# Panelizado_frentes.net
KiCad netlist of a schematic drawn in EAGLE
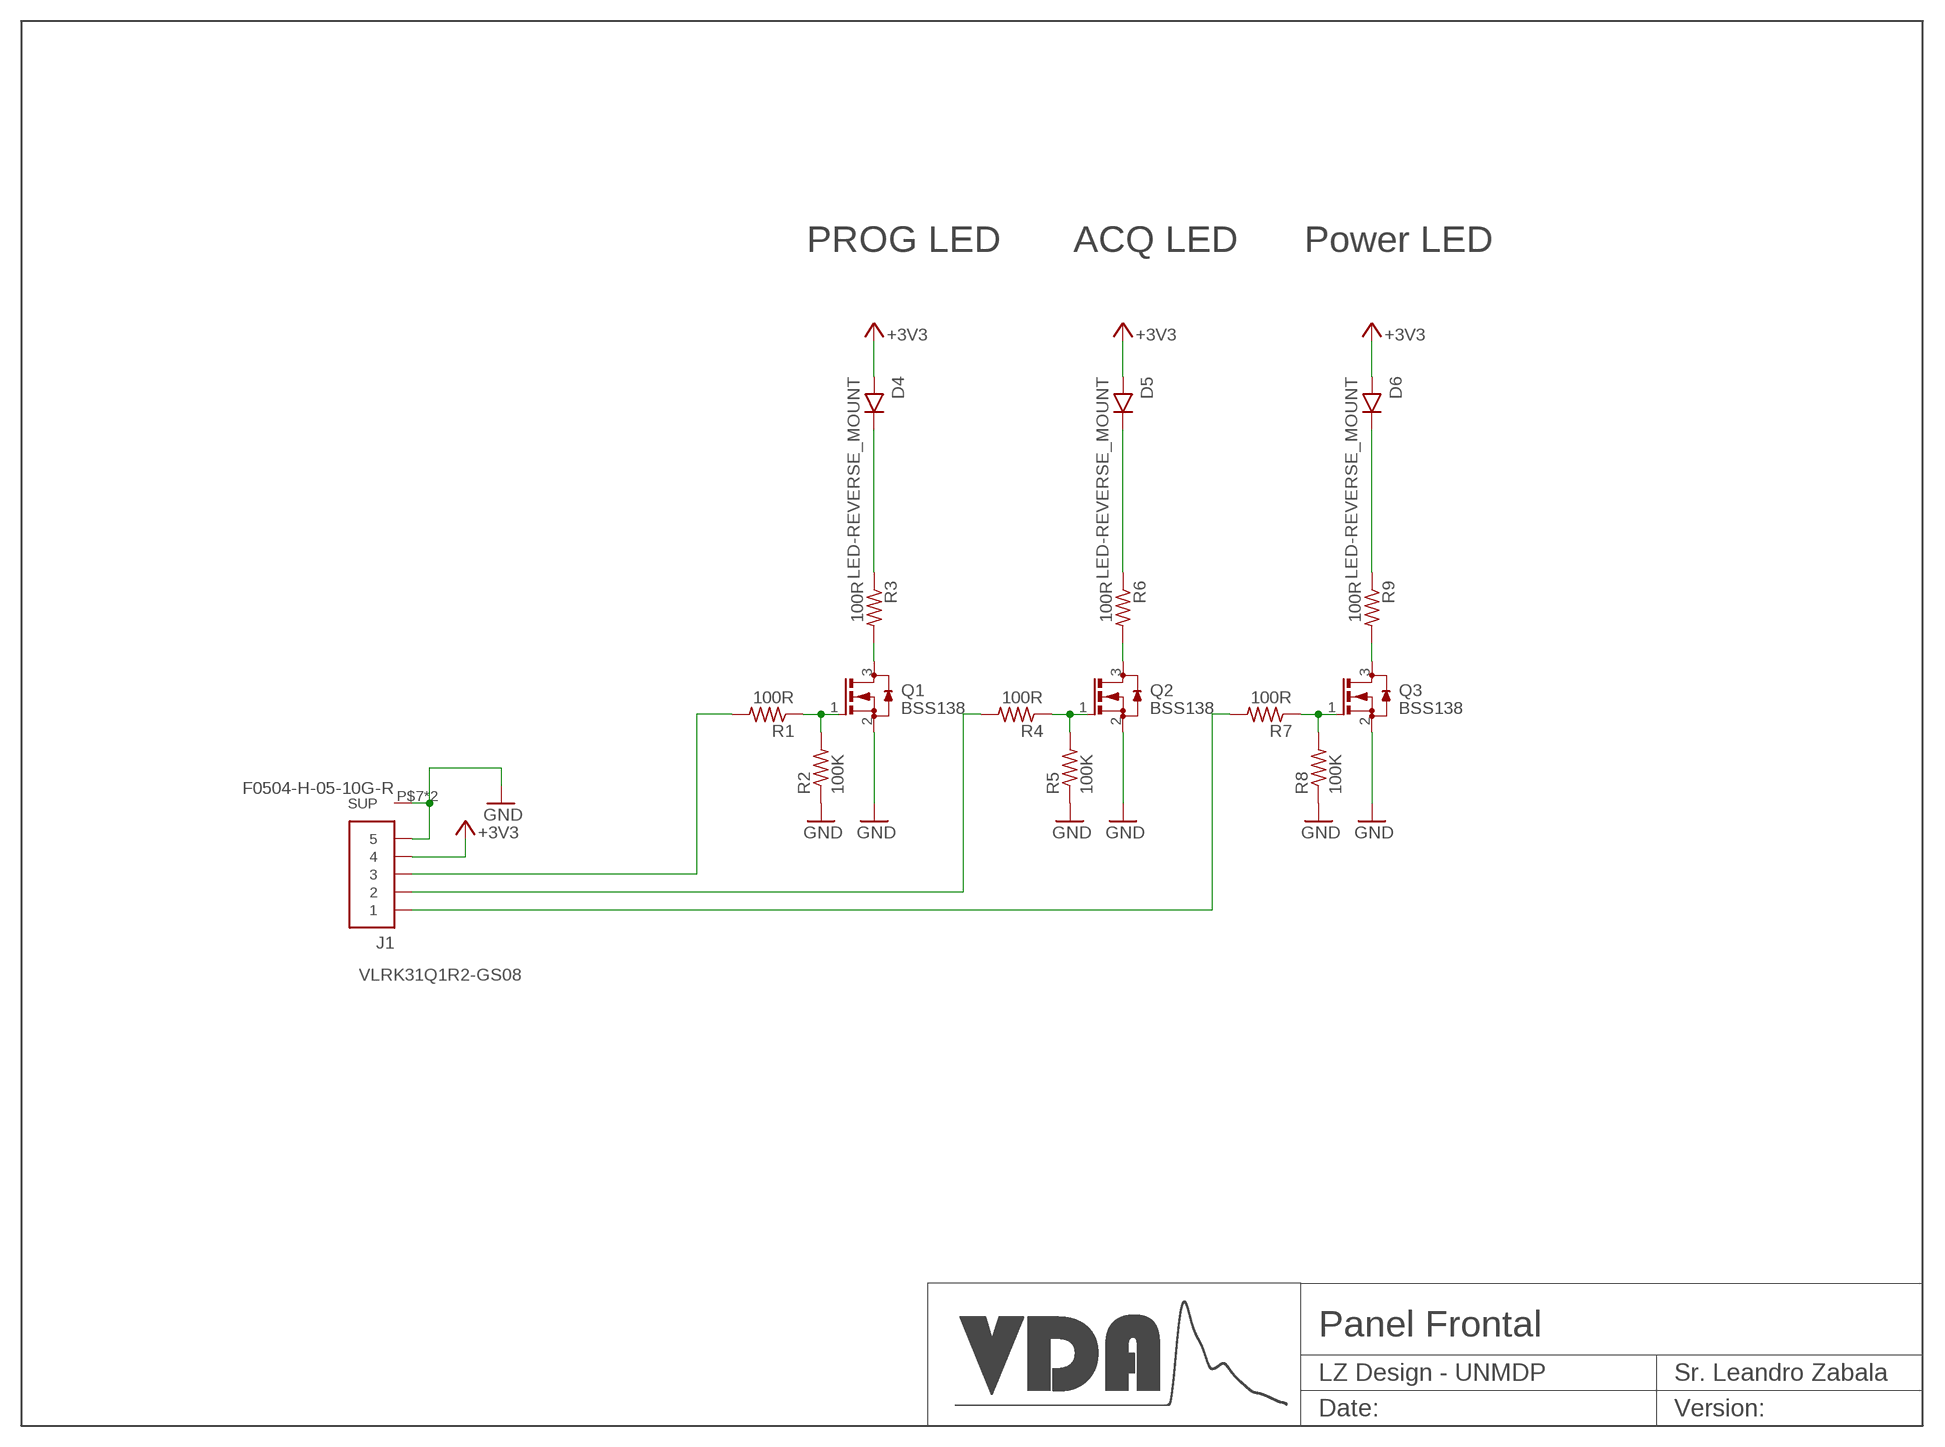
[diagram p0: schematic, sheet 1]
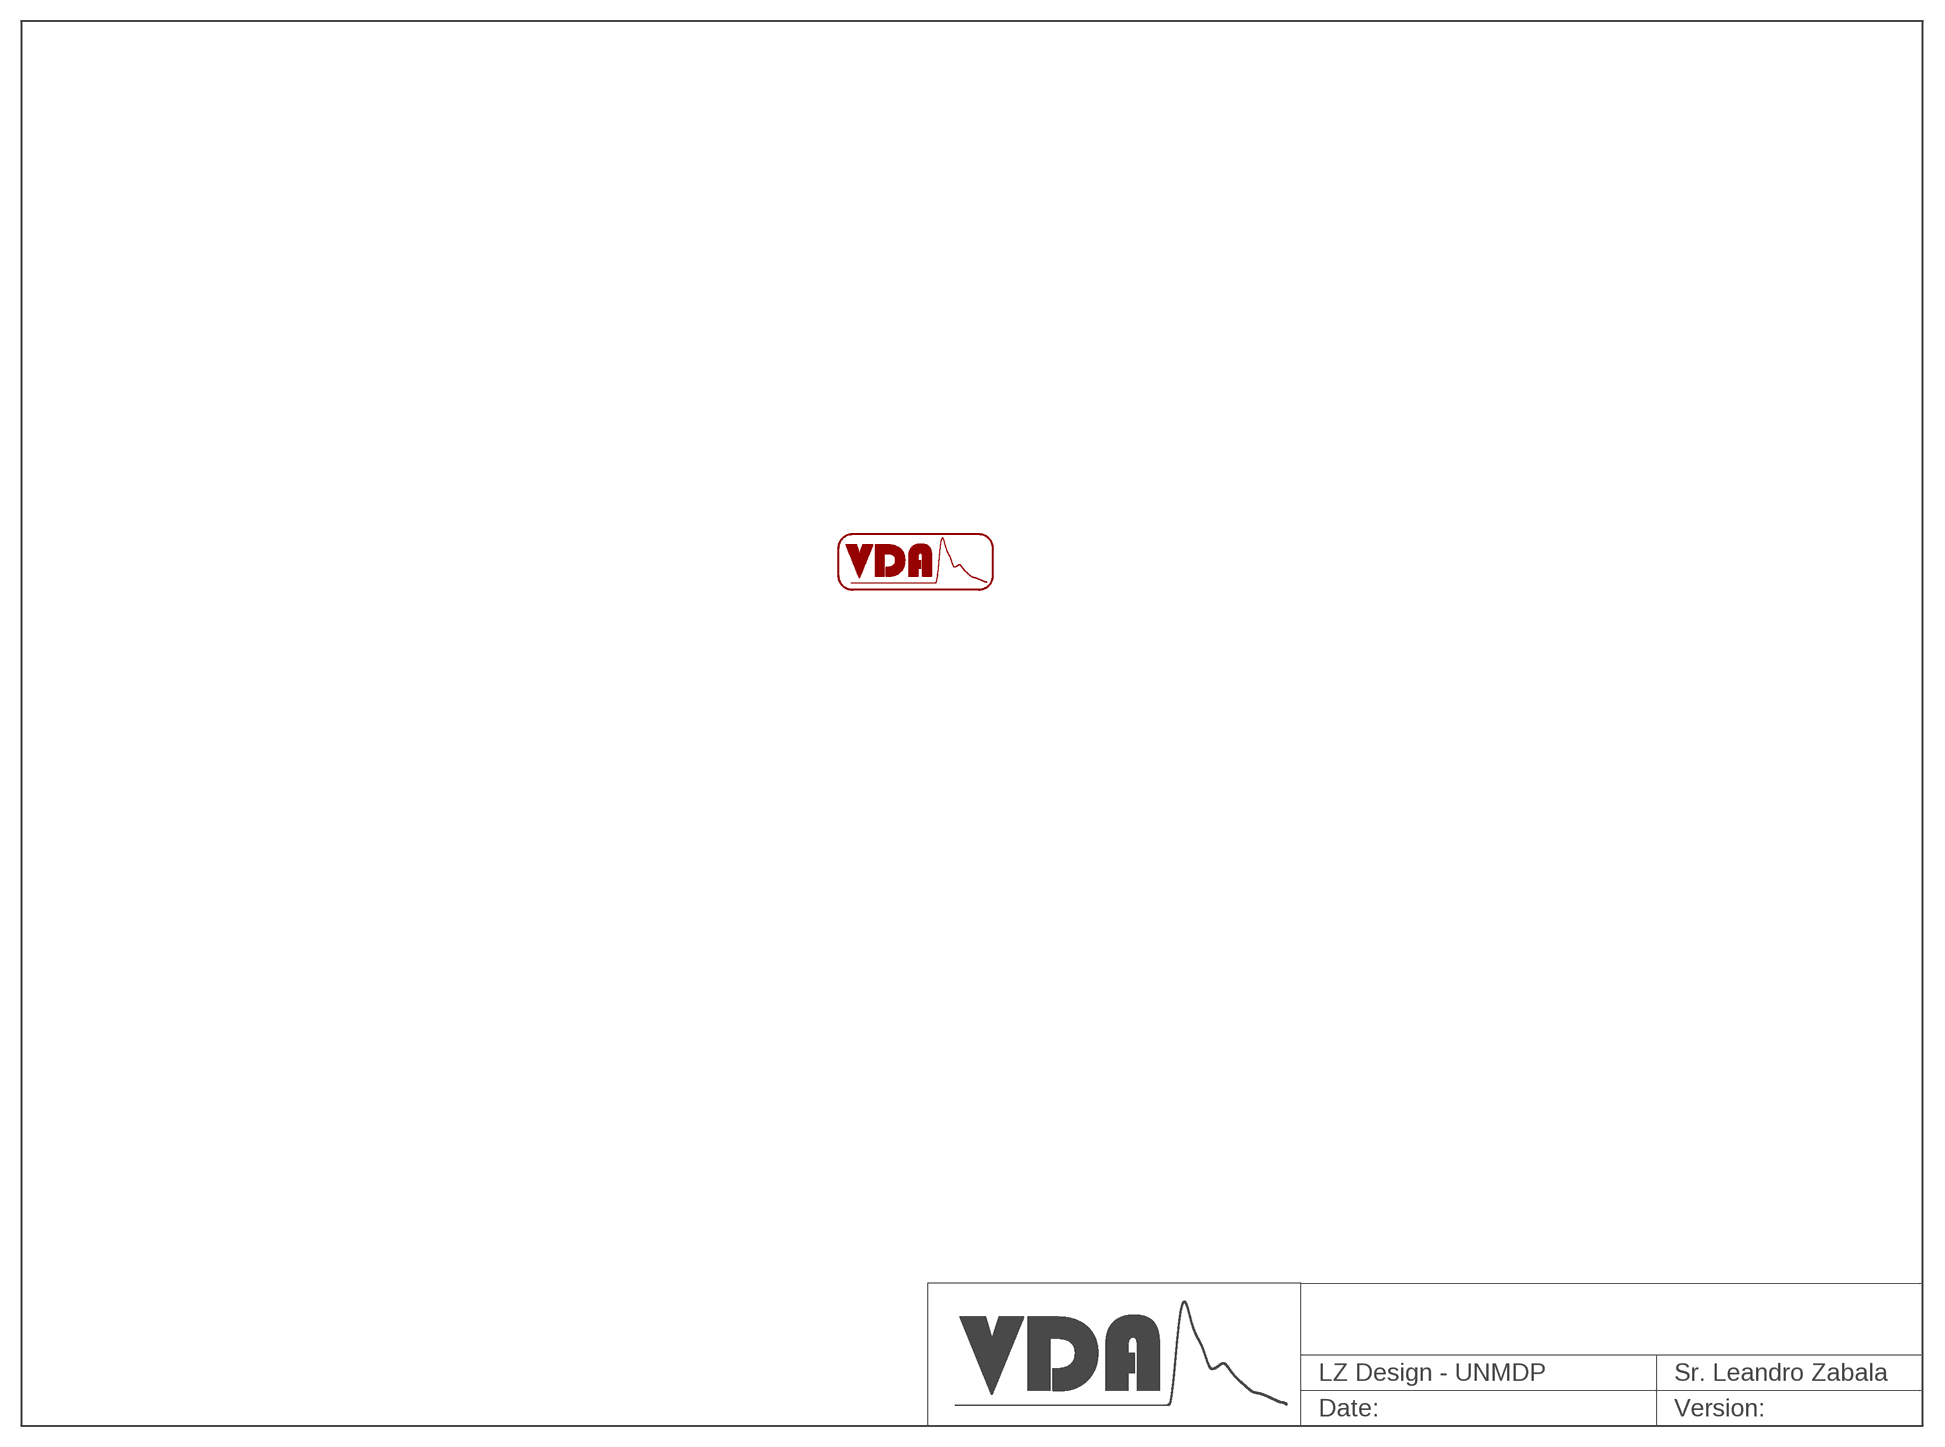
[diagram p1: schematic, sheet 2]

(export (version "E")
  (design (tool "Eeschema 10.0.6"))
  (components
    (comp (ref "U$1")
      (value "LOGO_VDA-3CM")
      (footprint "eagle-import:LOGO_VDA-3CM")
      (libsource (lib "eagle-import") (part "LOGO_VDA-3CM"))
    )
    (comp (ref "D4")
      (value "LED-REVERSE_MOUNT")
      (footprint "eagle-import:VLRK31")
      (libsource (lib "eagle-import") (part "LED-REVERSE_MOUNT"))
    )
    (comp (ref "D5")
      (value "LED-REVERSE_MOUNT")
      (footprint "eagle-import:VLRK31")
      (libsource (lib "eagle-import") (part "LED-REVERSE_MOUNT"))
    )
    (comp (ref "D6")
      (value "LED-REVERSE_MOUNT")
      (footprint "eagle-import:VLRK31")
      (libsource (lib "eagle-import") (part "LED-REVERSE_MOUNT"))
    )
    (comp (ref "J1")
      (value "F0504-H-05-10G-R")
      (footprint "eagle-import:F0504-H-05-10G-R")
      (libsource (lib "eagle-import") (part "F0504-H-05-10G-R"))
    )
    (comp (ref "Q1")
      (value "BSS138")
      (footprint "eagle-import:SOT-23")
      (libsource (lib "eagle-import") (part "N-MOS_SOT23-3"))
    )
    (comp (ref "Q2")
      (value "BSS138")
      (footprint "eagle-import:SOT-23")
      (libsource (lib "eagle-import") (part "N-MOS_SOT23-3"))
    )
    (comp (ref "Q3")
      (value "BSS138")
      (footprint "eagle-import:SOT-23")
      (libsource (lib "eagle-import") (part "N-MOS_SOT23-3"))
    )
    (comp (ref "R1")
      (value "100R")
      (footprint "eagle-import:R_0603")
      (libsource (lib "eagle-import") (part "R_0603"))
    )
    (comp (ref "R2")
      (value "100K")
      (footprint "eagle-import:R_0603")
      (libsource (lib "eagle-import") (part "R_0603"))
    )
    (comp (ref "R3")
      (value "100R")
      (footprint "eagle-import:R_0603")
      (libsource (lib "eagle-import") (part "R_0603"))
    )
    (comp (ref "R4")
      (value "100R")
      (footprint "eagle-import:R_0603")
      (libsource (lib "eagle-import") (part "R_0603"))
    )
    (comp (ref "R5")
      (value "100K")
      (footprint "eagle-import:R_0603")
      (libsource (lib "eagle-import") (part "R_0603"))
    )
    (comp (ref "R6")
      (value "100R")
      (footprint "eagle-import:R_0603")
      (libsource (lib "eagle-import") (part "R_0603"))
    )
    (comp (ref "R7")
      (value "100R")
      (footprint "eagle-import:R_0603")
      (libsource (lib "eagle-import") (part "R_0603"))
    )
    (comp (ref "R8")
      (value "100K")
      (footprint "eagle-import:R_0603")
      (libsource (lib "eagle-import") (part "R_0603"))
    )
    (comp (ref "R9")
      (value "100R")
      (footprint "eagle-import:R_0603")
      (libsource (lib "eagle-import") (part "R_0603"))
    )
  )
  (nets
    (net (code "1") (name "+3V3") (class "Default")
      (node (ref "D4") (pin "A") (pinfunction "A_A") (pintype "bidirectional"))
      (node (ref "D5") (pin "A") (pinfunction "A_A") (pintype "bidirectional"))
      (node (ref "D6") (pin "A") (pinfunction "A_A") (pintype "bidirectional"))
      (node (ref "J1") (pin "P$4") (pinfunction "4_P$4") (pintype "bidirectional"))
    )
    (net (code "2") (name "GND") (class "Default")
      (node (ref "J1") (pin "P$5") (pinfunction "5_P$5") (pintype "bidirectional"))
      (node (ref "J1") (pin "P$7") (pinfunction "SUP_P$7") (pintype "bidirectional"))
      (node (ref "J1") (pin "P$8") (pinfunction "SUP_P$8") (pintype "bidirectional"))
      (node (ref "Q1") (pin "2") (pinfunction "S_2") (pintype "passive"))
      (node (ref "Q2") (pin "2") (pinfunction "S_2") (pintype "passive"))
      (node (ref "Q3") (pin "2") (pinfunction "S_2") (pintype "passive"))
      (node (ref "R2") (pin "1") (pinfunction "1_1") (pintype "passive"))
      (node (ref "R5") (pin "1") (pinfunction "1_1") (pintype "passive"))
      (node (ref "R8") (pin "1") (pinfunction "1_1") (pintype "passive"))
    )
    (net (code "3") (name "Net-(D4-PadK)") (class "Default")
      (node (ref "D4") (pin "K") (pinfunction "K_K") (pintype "bidirectional"))
      (node (ref "R3") (pin "1") (pinfunction "1_1") (pintype "passive"))
    )
    (net (code "4") (name "Net-(D5-PadK)") (class "Default")
      (node (ref "D5") (pin "K") (pinfunction "K_K") (pintype "bidirectional"))
      (node (ref "R6") (pin "1") (pinfunction "1_1") (pintype "passive"))
    )
    (net (code "5") (name "Net-(D6-PadK)") (class "Default")
      (node (ref "D6") (pin "K") (pinfunction "K_K") (pintype "bidirectional"))
      (node (ref "R9") (pin "1") (pinfunction "1_1") (pintype "passive"))
    )
    (net (code "6") (name "Net-(J1-1)") (class "Default")
      (node (ref "J1") (pin "P$1") (pinfunction "1_P$1") (pintype "bidirectional"))
      (node (ref "R7") (pin "2") (pinfunction "2_2") (pintype "passive"))
    )
    (net (code "7") (name "Net-(J1-2)") (class "Default")
      (node (ref "J1") (pin "P$2") (pinfunction "2_P$2") (pintype "bidirectional"))
      (node (ref "R4") (pin "2") (pinfunction "2_2") (pintype "passive"))
    )
    (net (code "8") (name "Net-(J1-3)") (class "Default")
      (node (ref "J1") (pin "P$3") (pinfunction "3_P$3") (pintype "bidirectional"))
      (node (ref "R1") (pin "2") (pinfunction "2_2") (pintype "passive"))
    )
    (net (code "9") (name "Net-(Q1-D)") (class "Default")
      (node (ref "Q1") (pin "3") (pinfunction "D_3") (pintype "passive"))
      (node (ref "R3") (pin "2") (pinfunction "2_2") (pintype "passive"))
    )
    (net (code "10") (name "Net-(Q1-G)") (class "Default")
      (node (ref "Q1") (pin "1") (pinfunction "G_1") (pintype "passive"))
      (node (ref "R1") (pin "1") (pinfunction "1_1") (pintype "passive"))
      (node (ref "R2") (pin "2") (pinfunction "2_2") (pintype "passive"))
    )
    (net (code "11") (name "Net-(Q2-D)") (class "Default")
      (node (ref "Q2") (pin "3") (pinfunction "D_3") (pintype "passive"))
      (node (ref "R6") (pin "2") (pinfunction "2_2") (pintype "passive"))
    )
    (net (code "12") (name "Net-(Q2-G)") (class "Default")
      (node (ref "Q2") (pin "1") (pinfunction "G_1") (pintype "passive"))
      (node (ref "R4") (pin "1") (pinfunction "1_1") (pintype "passive"))
      (node (ref "R5") (pin "2") (pinfunction "2_2") (pintype "passive"))
    )
    (net (code "13") (name "Net-(Q3-D)") (class "Default")
      (node (ref "Q3") (pin "3") (pinfunction "D_3") (pintype "passive"))
      (node (ref "R9") (pin "2") (pinfunction "2_2") (pintype "passive"))
    )
    (net (code "14") (name "Net-(Q3-G)") (class "Default")
      (node (ref "Q3") (pin "1") (pinfunction "G_1") (pintype "passive"))
      (node (ref "R7") (pin "1") (pinfunction "1_1") (pintype "passive"))
      (node (ref "R8") (pin "2") (pinfunction "2_2") (pintype "passive"))
    )
  )
)
